# Doorbellv1_2.net
KiCad netlist of a schematic drawn in Altium Designer
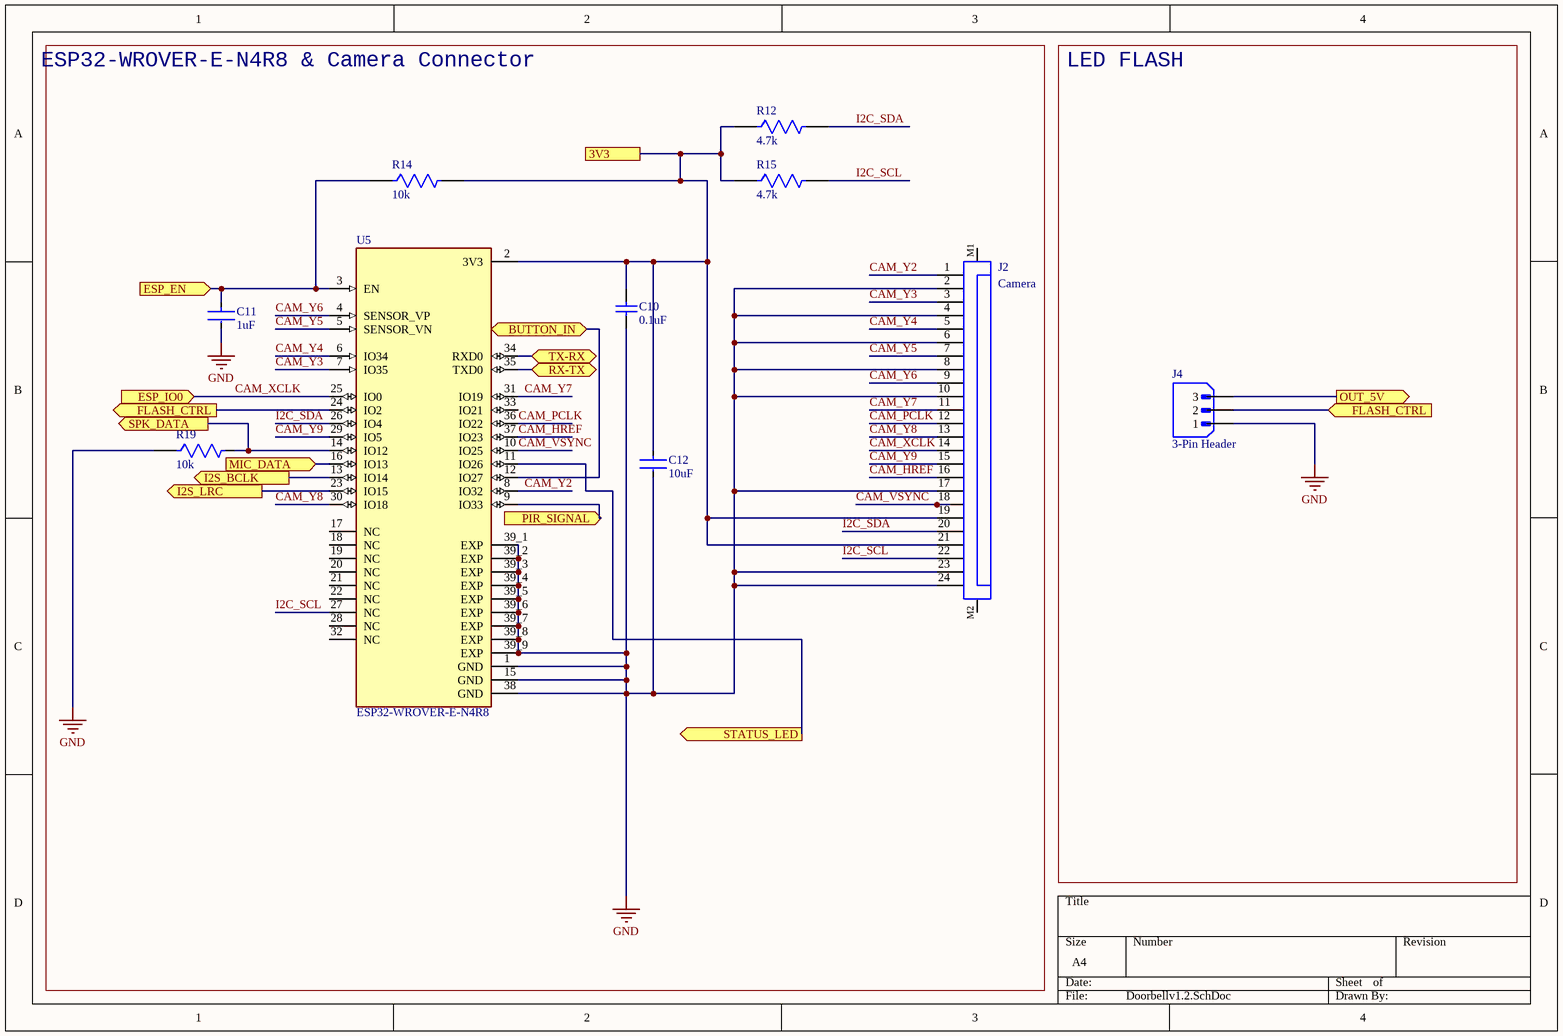
[diagram p0: Doorbellv1.2.SchDoc]

(export (version "E")
  (design (tool "Eeschema 10.0.6"))
  (components
    (comp (ref "C10")
      (value "0.1uF")
      (footprint "CAPC1608X90X35NL15T15")
      (fields (field (name "PART NUMBER") "C0603C104K4RAC7013") (field (name "MANUFACTURER") "Kemet"))
      (libsource (lib "Altium Content Vault") (part "CAP"))
    )
    (comp (ref "C11")
      (value "1uF")
      (footprint "FP-CC0603-DA-MFG")
      (description "CAP CER 1UF 25V X5R 0603")
      (fields
        (field (name "OCTOPART") "https://octopart.com/cc0603mrx5r8bb105-yageo-57080766")
        (field (name "VOLTAGE") "25 V")
      )
      (libsource (lib "Altium Content Vault") (part "11868f565c42a9108669ba33697ecf6"))
    )
    (comp (ref "C12")
      (value "10uF")
      (footprint "FP-C0603C106M8PACTU-MFG")
      (description "CAP CER 10UF 10V X5R 0603")
      (libsource (lib "Altium Content Vault") (part "02cd4be3c70576c341d710602a673aa"))
    )
    (comp (ref "J2")
      (value "Camera")
      (footprint "68712414522")
      (description "Ffc/fpc Conn, R/a Rcpt, 24POS, 1ROW, SMT Rohs Compliant: Yes")
      (libsource (lib "Altium Content Vault") (part "FPC - 24P - 2MP"))
    )
    (comp (ref "J4")
      (value "3-Pin Header")
      (footprint "JST_B3B-XH-A")
      (description "Connector Header Through Hole 3 position 0.098 (2.50mm)")
      (fields (field (name "MF") "JST Sales") (field (name "MP") "B3B-XH-A"))
      (libsource (lib "B3B-XH-A (1)") (part "B3B-XH-A"))
    )
    (comp (ref "R12")
      (value "4.7k")
      (footprint "FP-TFCR0603-IPC_B")
      (description "RES Thin Film,  4.7kΩ, 1%, 0.1W, 50ppm/°C, 0603")
      (libsource (lib "Altium Content Vault") (part "1029c3af85768c4190bb7ad29bc67b5"))
    )
    (comp (ref "R14")
      (value "10k")
      (footprint "FP-MCT0603-IPC_B")
      (description "RES SMD 100 OHM 1% 1/8W 0603")
      (libsource (lib "Altium Content Vault") (part "1029c3af85768c4190bb7ad29bc67b5"))
    )
    (comp (ref "R15")
      (value "4.7k")
      (footprint "FP-TFCR0603-IPC_B")
      (description "RES Thin Film,  4.7kΩ, 1%, 0.1W, 50ppm/°C, 0603")
      (libsource (lib "Altium Content Vault") (part "1029c3af85768c4190bb7ad29bc67b5"))
    )
    (comp (ref "R19")
      (value "10k")
      (footprint "FP-MCT0603-IPC_B")
      (description "RES SMD 100 OHM 1% 1/8W 0603")
      (libsource (lib "Altium Content Vault") (part "1029c3af85768c4190bb7ad29bc67b5"))
    )
    (comp (ref "U5")
      (value "ESP32-WROVER-E-N4R8")
      (footprint "XCVR_ESP32-WROVER-E-N4R8")
      (fields (field (name "MF") "Espressif Systems"))
      (libsource (lib "ESP32-WROVER-E-N4R8 (1)") (part "ESP32-WROVER-E-N4R8"))
    )
  )
  (nets
    (net (code "1") (name "/3V3") (class "Default")
      (node (ref "C10") (pin "1") (pinfunction "1_1") (pintype "passive"))
      (node (ref "C12") (pin "1") (pinfunction "1_1") (pintype "passive"))
      (node (ref "J2") (pin "19") (pinfunction "19_19") (pintype "passive"))
      (node (ref "J2") (pin "21") (pinfunction "21_21") (pintype "passive"))
      (node (ref "R12") (pin "1") (pinfunction "1_1") (pintype "passive"))
      (node (ref "R14") (pin "2") (pinfunction "2_2") (pintype "passive"))
      (node (ref "R15") (pin "1") (pinfunction "1_1") (pintype "passive"))
      (node (ref "U5") (pin "2") (pinfunction "3V3_2") (pintype "power_in"))
    )
    (net (code "2") (name "/BUTTON_IN") (class "Default")
      (node (ref "U5") (pin "12") (pinfunction "IO27_12") (pintype "bidirectional"))
    )
    (net (code "3") (name "/CAM_HREF") (class "Default")
      (node (ref "J2") (pin "16") (pinfunction "16_16") (pintype "passive"))
      (node (ref "U5") (pin "37") (pinfunction "IO23_37") (pintype "bidirectional"))
    )
    (net (code "4") (name "/CAM_PCLK") (class "Default")
      (node (ref "J2") (pin "12") (pinfunction "12_12") (pintype "passive"))
      (node (ref "U5") (pin "36") (pinfunction "IO22_36") (pintype "bidirectional"))
    )
    (net (code "5") (name "/CAM_VSYNC") (class "Default")
      (node (ref "J2") (pin "18") (pinfunction "18_18") (pintype "passive"))
      (node (ref "U5") (pin "10") (pinfunction "IO25_10") (pintype "bidirectional"))
    )
    (net (code "6") (name "/CAM_XCLK") (class "Default")
      (node (ref "J2") (pin "14") (pinfunction "14_14") (pintype "passive"))
      (node (ref "U5") (pin "25") (pinfunction "IO0_25") (pintype "bidirectional"))
    )
    (net (code "7") (name "/CAM_Y2") (class "Default")
      (node (ref "J2") (pin "1") (pinfunction "1_1") (pintype "passive"))
      (node (ref "U5") (pin "8") (pinfunction "IO32_8") (pintype "bidirectional"))
    )
    (net (code "8") (name "/CAM_Y3") (class "Default")
      (node (ref "J2") (pin "3") (pinfunction "3_3") (pintype "passive"))
      (node (ref "U5") (pin "7") (pinfunction "IO35_7") (pintype "input"))
    )
    (net (code "9") (name "/CAM_Y4") (class "Default")
      (node (ref "J2") (pin "5") (pinfunction "5_5") (pintype "passive"))
      (node (ref "U5") (pin "6") (pinfunction "IO34_6") (pintype "input"))
    )
    (net (code "10") (name "/CAM_Y5") (class "Default")
      (node (ref "J2") (pin "7") (pinfunction "7_7") (pintype "passive"))
      (node (ref "U5") (pin "5") (pinfunction "SENSOR_VN_5") (pintype "input"))
    )
    (net (code "11") (name "/CAM_Y6") (class "Default")
      (node (ref "J2") (pin "9") (pinfunction "9_9") (pintype "passive"))
      (node (ref "U5") (pin "4") (pinfunction "SENSOR_VP_4") (pintype "input"))
    )
    (net (code "12") (name "/CAM_Y7") (class "Default")
      (node (ref "J2") (pin "11") (pinfunction "11_11") (pintype "passive"))
      (node (ref "U5") (pin "31") (pinfunction "IO19_31") (pintype "bidirectional"))
    )
    (net (code "13") (name "/CAM_Y8") (class "Default")
      (node (ref "J2") (pin "13") (pinfunction "13_13") (pintype "passive"))
      (node (ref "U5") (pin "30") (pinfunction "IO18_30") (pintype "bidirectional"))
    )
    (net (code "14") (name "/CAM_Y9") (class "Default")
      (node (ref "J2") (pin "15") (pinfunction "15_15") (pintype "passive"))
      (node (ref "U5") (pin "29") (pinfunction "IO5_29") (pintype "bidirectional"))
    )
    (net (code "15") (name "/ESP_EN") (class "Default")
      (node (ref "C11") (pin "1") (pinfunction "1_1") (pintype "passive"))
      (node (ref "R14") (pin "1") (pinfunction "1_1") (pintype "passive"))
      (node (ref "U5") (pin "3") (pinfunction "EN_3") (pintype "input"))
    )
    (net (code "16") (name "/FLASH_CTRL") (class "Default")
      (node (ref "J4") (pin "2") (pinfunction "2_2") (pintype "passive"))
      (node (ref "U5") (pin "24") (pinfunction "IO2_24") (pintype "bidirectional"))
    )
    (net (code "17") (name "/I2C_SCL") (class "Default")
      (node (ref "J2") (pin "22") (pinfunction "22_22") (pintype "passive"))
      (node (ref "R15") (pin "2") (pinfunction "2_2") (pintype "passive"))
      (node (ref "U5") (pin "27") (pinfunction "NC_27") (pintype "passive"))
    )
    (net (code "18") (name "/I2C_SDA") (class "Default")
      (node (ref "J2") (pin "20") (pinfunction "20_20") (pintype "passive"))
      (node (ref "R12") (pin "2") (pinfunction "2_2") (pintype "passive"))
      (node (ref "U5") (pin "26") (pinfunction "IO4_26") (pintype "bidirectional"))
    )
    (net (code "19") (name "/I2S_BCLK") (class "Default")
      (node (ref "U5") (pin "13") (pinfunction "IO14_13") (pintype "bidirectional"))
    )
    (net (code "20") (name "/I2S_LRC") (class "Default")
      (node (ref "U5") (pin "23") (pinfunction "IO15_23") (pintype "bidirectional"))
    )
    (net (code "21") (name "/MIC_DATA") (class "Default")
      (node (ref "U5") (pin "16") (pinfunction "IO13_16") (pintype "bidirectional"))
    )
    (net (code "22") (name "/OUT_5V") (class "Default")
      (node (ref "J4") (pin "3") (pinfunction "3_3") (pintype "passive"))
    )
    (net (code "23") (name "/PIR_SIGNAL") (class "Default")
      (node (ref "U5") (pin "9") (pinfunction "IO33_9") (pintype "bidirectional"))
    )
    (net (code "24") (name "/RX-TX") (class "Default")
      (node (ref "U5") (pin "35") (pinfunction "TXD0_35") (pintype "bidirectional"))
    )
    (net (code "25") (name "/SPK_DATA") (class "Default")
      (node (ref "R19") (pin "2") (pinfunction "2_2") (pintype "passive"))
      (node (ref "U5") (pin "14") (pinfunction "IO12_14") (pintype "bidirectional"))
    )
    (net (code "26") (name "/STATUS_LED") (class "Default")
      (node (ref "U5") (pin "11") (pinfunction "IO26_11") (pintype "bidirectional"))
    )
    (net (code "27") (name "/TX-RX") (class "Default")
      (node (ref "U5") (pin "34") (pinfunction "RXD0_34") (pintype "bidirectional"))
    )
    (net (code "28") (name "GND") (class "Default")
      (node (ref "C10") (pin "2") (pinfunction "2_2") (pintype "passive"))
      (node (ref "C11") (pin "2") (pinfunction "2_2") (pintype "passive"))
      (node (ref "C12") (pin "2") (pinfunction "2_2") (pintype "passive"))
      (node (ref "J2") (pin "10") (pinfunction "10_10") (pintype "passive"))
      (node (ref "J2") (pin "17") (pinfunction "17_17") (pintype "passive"))
      (node (ref "J2") (pin "2") (pinfunction "2_2") (pintype "passive"))
      (node (ref "J2") (pin "23") (pinfunction "23_23") (pintype "passive"))
      (node (ref "J2") (pin "24") (pinfunction "24_24") (pintype "passive"))
      (node (ref "J2") (pin "4") (pinfunction "4_4") (pintype "passive"))
      (node (ref "J2") (pin "6") (pinfunction "6_6") (pintype "passive"))
      (node (ref "J2") (pin "8") (pinfunction "8_8") (pintype "passive"))
      (node (ref "J4") (pin "1") (pinfunction "1_1") (pintype "passive"))
      (node (ref "R19") (pin "1") (pinfunction "1_1") (pintype "passive"))
      (node (ref "U5") (pin "1") (pinfunction "GND_1") (pintype "power_in"))
      (node (ref "U5") (pin "15") (pinfunction "GND_15") (pintype "power_in"))
      (node (ref "U5") (pin "38") (pinfunction "GND_38") (pintype "power_in"))
      (node (ref "U5") (pin "39_1") (pinfunction "EXP_39_1") (pintype "power_in"))
      (node (ref "U5") (pin "39_2") (pinfunction "EXP_39_2") (pintype "power_in"))
      (node (ref "U5") (pin "39_3") (pinfunction "EXP_39_3") (pintype "power_in"))
      (node (ref "U5") (pin "39_4") (pinfunction "EXP_39_4") (pintype "power_in"))
      (node (ref "U5") (pin "39_5") (pinfunction "EXP_39_5") (pintype "power_in"))
      (node (ref "U5") (pin "39_6") (pinfunction "EXP_39_6") (pintype "power_in"))
      (node (ref "U5") (pin "39_7") (pinfunction "EXP_39_7") (pintype "power_in"))
      (node (ref "U5") (pin "39_8") (pinfunction "EXP_39_8") (pintype "power_in"))
      (node (ref "U5") (pin "39_9") (pinfunction "EXP_39_9") (pintype "power_in"))
    )
    (net (code "29") (name "unconnected-(J2-PadM1)") (class "Default")
      (node (ref "J2") (pin "M1") (pinfunction "M1_M1") (pintype "passive"))
    )
    (net (code "30") (name "unconnected-(J2-PadM2)") (class "Default")
      (node (ref "J2") (pin "M2") (pinfunction "M2_M2") (pintype "passive"))
    )
    (net (code "31") (name "unconnected-(U5-IO21-Pad33)") (class "Default")
      (node (ref "U5") (pin "33") (pinfunction "IO21_33") (pintype "bidirectional"))
    )
    (net (code "32") (name "unconnected-(U5-NC-Pad17)") (class "Default")
      (node (ref "U5") (pin "17") (pinfunction "NC_17") (pintype "passive"))
    )
    (net (code "33") (name "unconnected-(U5-NC-Pad18)") (class "Default")
      (node (ref "U5") (pin "18") (pinfunction "NC_18") (pintype "passive"))
    )
    (net (code "34") (name "unconnected-(U5-NC-Pad19)") (class "Default")
      (node (ref "U5") (pin "19") (pinfunction "NC_19") (pintype "passive"))
    )
    (net (code "35") (name "unconnected-(U5-NC-Pad20)") (class "Default")
      (node (ref "U5") (pin "20") (pinfunction "NC_20") (pintype "passive"))
    )
    (net (code "36") (name "unconnected-(U5-NC-Pad21)") (class "Default")
      (node (ref "U5") (pin "21") (pinfunction "NC_21") (pintype "passive"))
    )
    (net (code "37") (name "unconnected-(U5-NC-Pad22)") (class "Default")
      (node (ref "U5") (pin "22") (pinfunction "NC_22") (pintype "passive"))
    )
    (net (code "38") (name "unconnected-(U5-NC-Pad28)") (class "Default")
      (node (ref "U5") (pin "28") (pinfunction "NC_28") (pintype "passive"))
    )
    (net (code "39") (name "unconnected-(U5-NC-Pad32)") (class "Default")
      (node (ref "U5") (pin "32") (pinfunction "NC_32") (pintype "passive"))
    )
  )
)
